# AST1028.net
KiCad netlist of a schematic drawn in EAGLE
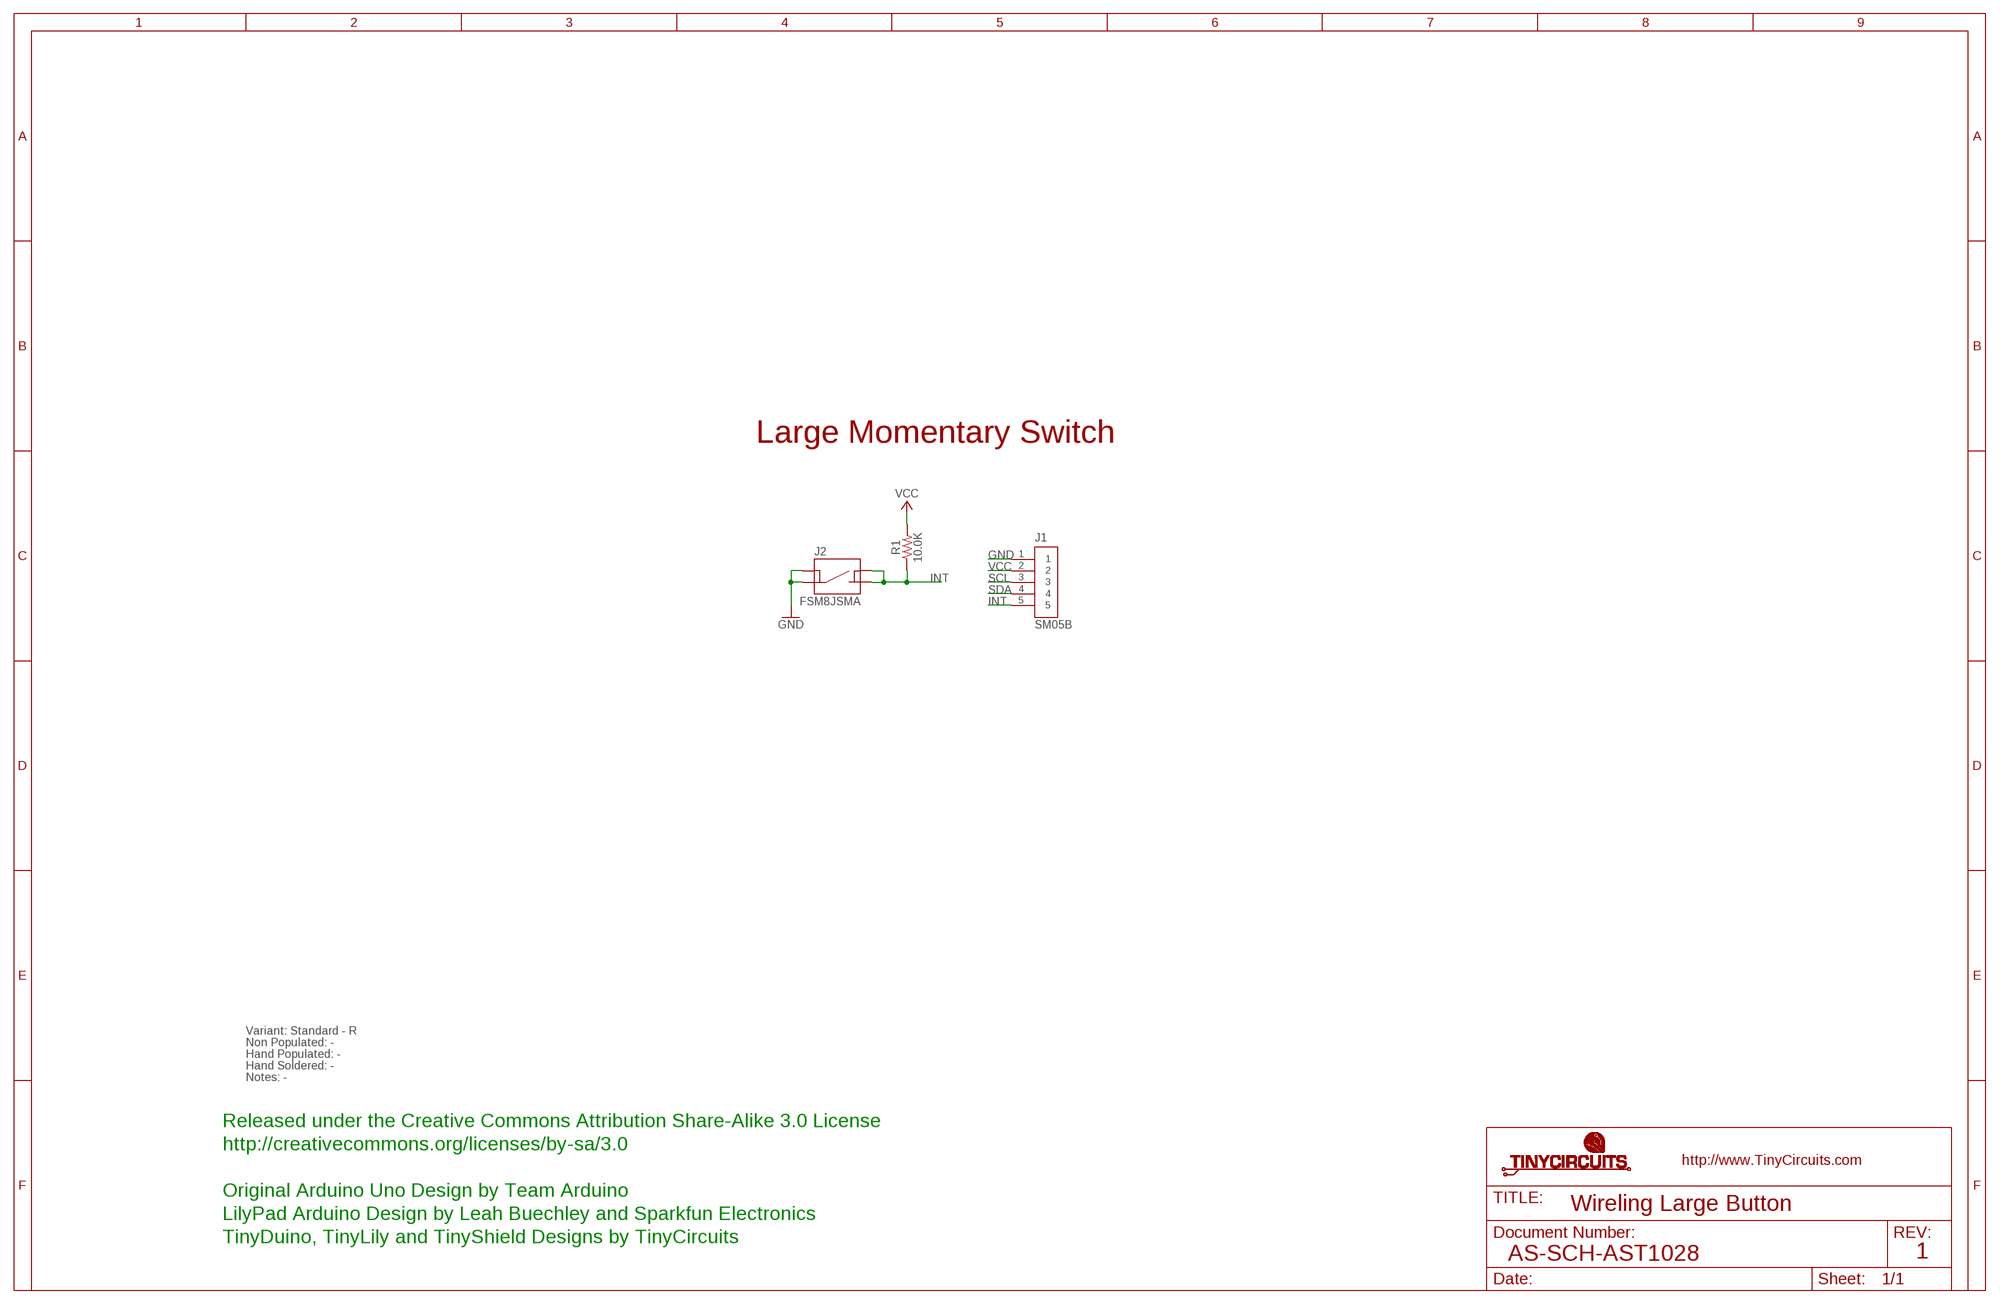
[diagram p0: schematic, sheet 1]

(export (version "E")
  (design (tool "Eeschema 10.0.6"))
  (components
    (comp (ref "J1")
      (value "SM05B")
      (footprint "eagle-import:JST_SH_5X1_EDGE")
      (fields (field (name "PARTNO") "AS-ITM-00340"))
      (libsource (lib "eagle-import") (part "AS-ITM-00340EDGE"))
    )
    (comp (ref "J2")
      (value "FSM8JSMA")
      (footprint "eagle-import:SWITCH-FSM_JSM")
      (fields (field (name "PARTNO") "AS-ITM-00278"))
      (libsource (lib "eagle-import") (part "AS-ITM-00278"))
    )
    (comp (ref "R1")
      (value "10.0K")
      (footprint "eagle-import:0402")
      (fields (field (name "PARTNO") "AS-ITM-00032"))
      (libsource (lib "eagle-import") (part "AS-ITM-00032"))
    )
  )
  (nets
    (net (code "1") (name "/INT") (class "Default")
      (node (ref "J1") (pin "5") (pinfunction "5_5") (pintype "bidirectional"))
      (node (ref "J2") (pin "P$2") (pinfunction "4_P$2") (pintype "bidirectional"))
      (node (ref "J2") (pin "P$3") (pinfunction "2_P$3") (pintype "bidirectional"))
      (node (ref "R1") (pin "1") (pinfunction "1_1") (pintype "passive"))
    )
    (net (code "2") (name "/SCL") (class "Default")
      (node (ref "J1") (pin "3") (pinfunction "3_3") (pintype "bidirectional"))
    )
    (net (code "3") (name "/SDA") (class "Default")
      (node (ref "J1") (pin "4") (pinfunction "4_4") (pintype "bidirectional"))
    )
    (net (code "4") (name "GND") (class "Default")
      (node (ref "J1") (pin "1") (pinfunction "1_1") (pintype "bidirectional"))
      (node (ref "J2") (pin "P$1") (pinfunction "3_P$1") (pintype "bidirectional"))
      (node (ref "J2") (pin "P$4") (pinfunction "1_P$4") (pintype "bidirectional"))
    )
    (net (code "5") (name "VCC") (class "Default")
      (node (ref "J1") (pin "2") (pinfunction "2_2") (pintype "bidirectional"))
      (node (ref "R1") (pin "2") (pinfunction "2_2") (pintype "passive"))
    )
  )
)
